# 07-GPS.net
KiCad netlist of a schematic drawn in Altium Designer
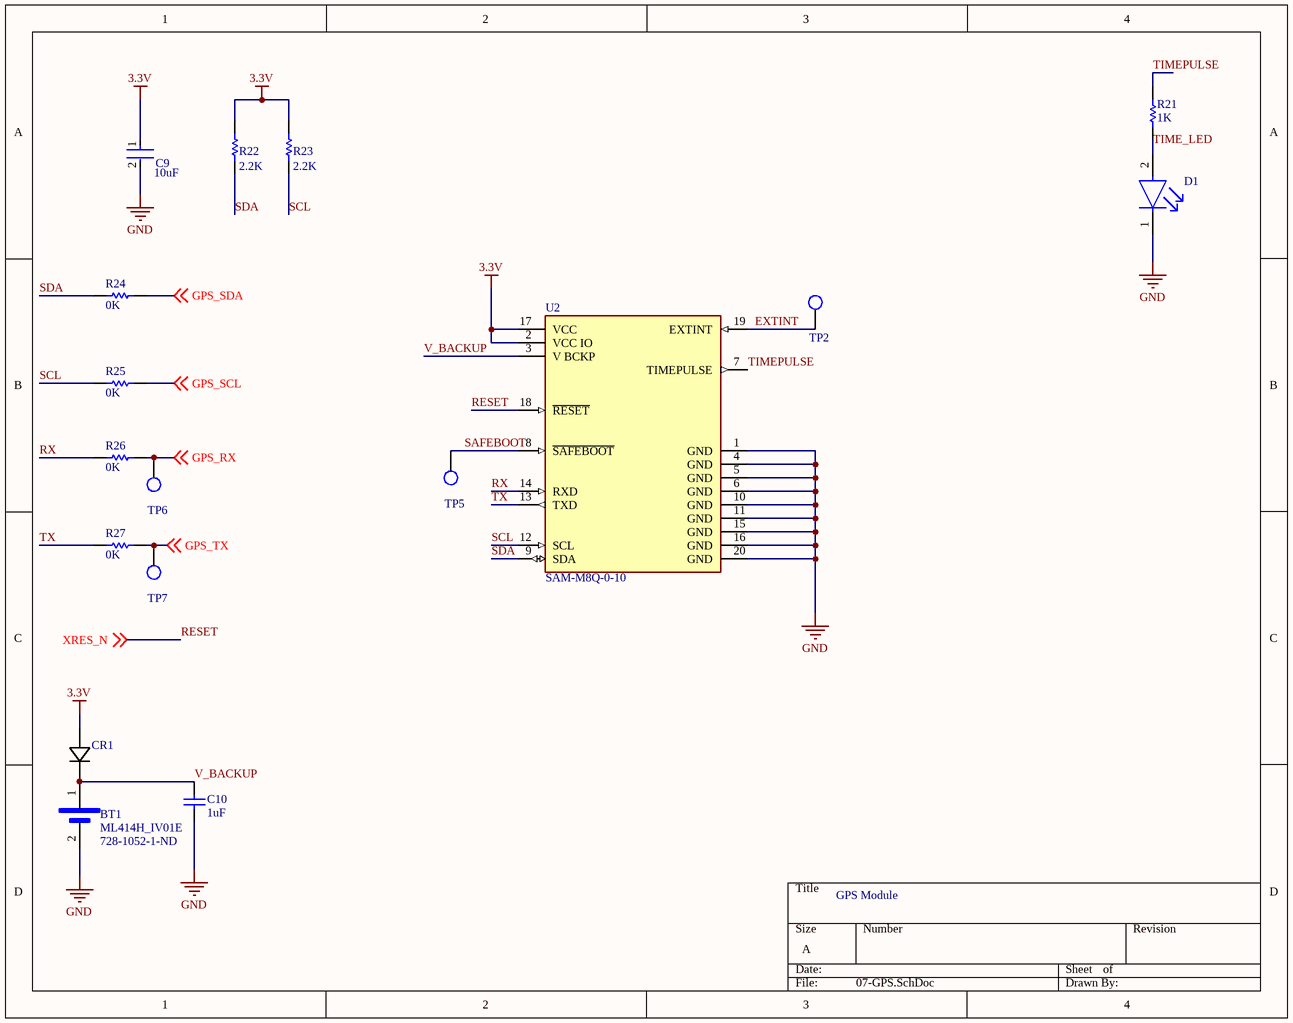
[diagram p0: 07-GPS.SchDoc]

(export (version "E")
  (design (tool "Eeschema 10.0.6"))
  (components
    (comp (ref "BT1")
      (value "ML414H_IV01E")
      (footprint "team6:SEIKO_ML414H_IV01E")
      (description "Coin, 4.8mm 3V Lithium Battery Rechargeable _Secondary_ 1mAh")
      (fields
        (field (name "MP") "ML414H IV01E")
        (field (name "MF") "Seiko Instruments")
        (field (name "SUPPLIER PART NUMBER 1") "728-1052-1-ND")
      )
      (libsource (lib "team6") (part "ML414H_IV01E"))
    )
    (comp (ref "C9")
      (value "CL21A106KQCLNNC")
      (footprint "FP-CL21-IPC_B")
      (description "CL21 Series 0805 10uF 6.3V ±10% Tolerance X5R Multilayer Ceramic Chip Capacitor")
      (fields (field (name "CAPACITANCE") "10uF") (field (name "TOLERANCE") "10%"))
      (libsource (lib "Altium Content Vault") (part "b4654b650e69147ec39a6b967a45e02"))
    )
    (comp (ref "C10")
      (value "1uF")
      (footprint "CAPC2013X145X50LL20T25")
      (fields (field (name "MANUFACTURER") "Kemet") (field (name "PART NUMBER") "C0805C105K4PACTU"))
      (libsource (lib "Altium Content Vault") (part "CAP"))
    )
    (comp (ref "CR1")
      (value "CUS05S40")
      (footprint "USC_TOS")
      (description "No Description Available")
      (fields (field (name "COPYRIGHT") "Copyright (C) 2022 Ultra Librarian. All rights reserved."))
      (libsource (lib "team6") (part "CUS05S40"))
    )
    (comp (ref "D1")
      (value "APHCM2012SYCK-F01")
      (footprint "FP-APHCM2012SYCK-F01-MFG")
      (description "LED YELLOW CLEAR CHIP SMD")
      (libsource (lib "Altium Content Vault") (part "8706943c75ba83719d021d2fdc84c58"))
    )
    (comp (ref "R21")
      (value "1K")
      (footprint "RESC2013X60X35ML10T20")
      (description "Chip Resistor, 1 KOhm, +/- 1%, 125 mW, -55 to 155 degC, 0805 (2012 Metric), RoHS, Tape and Reel")
      (fields (field (name "TOLERANCE") "1%") (field (name "MANUFACTURER") "Yageo"))
      (libsource (lib "Altium Content Vault") (part "RES-2"))
    )
    (comp (ref "R22")
      (value "2.2K")
      (footprint "RESC2013X70X40LL20T20")
      (description "ERJ-6GEYJ222V")
      (fields (field (name "MANUFACTURER") "Panasonic"))
      (libsource (lib "Altium Content Vault") (part "RES"))
    )
    (comp (ref "R23")
      (value "2.2K")
      (footprint "RESC2013X70X40LL20T20")
      (description "ERJ-6GEYJ222V")
      (fields (field (name "MANUFACTURER") "Panasonic"))
      (libsource (lib "Altium Content Vault") (part "RES"))
    )
    (comp (ref "R24")
      (value "0K")
      (footprint "RESC2013X50X30LL20T20")
      (fields (field (name "MANUFACTURER") "Vishay Dale") (field (name "PART NUMBER") "CRCW08050000Z0EA"))
      (libsource (lib "Altium Content Vault") (part "RES"))
    )
    (comp (ref "R25")
      (value "0K")
      (footprint "RESC2013X50X30LL20T20")
      (fields (field (name "MANUFACTURER") "Vishay Dale") (field (name "PART NUMBER") "CRCW08050000Z0EA"))
      (libsource (lib "Altium Content Vault") (part "RES"))
    )
    (comp (ref "R26")
      (value "0K")
      (footprint "RESC2013X50X30LL20T20")
      (fields (field (name "MANUFACTURER") "Vishay Dale") (field (name "PART NUMBER") "CRCW08050000Z0EA"))
      (libsource (lib "Altium Content Vault") (part "RES"))
    )
    (comp (ref "R27")
      (value "0K")
      (footprint "RESC2013X50X30LL20T20")
      (fields (field (name "MANUFACTURER") "Vishay Dale") (field (name "PART NUMBER") "CRCW08050000Z0EA"))
      (libsource (lib "Altium Content Vault") (part "RES"))
    )
    (comp (ref "TP2")
      (value "TP_1206")
      (footprint "TP-SMC-1206")
      (description "Test Point SMD 1206")
      (fields
        (field (name "MANUFACTURER") "TE Connectivity (Tyco Electronics)")
        (field (name "MANUFACTURER PART NUMBER") "1625854-1")
      )
      (libsource (lib "Mechanical") (part "TP_1206"))
    )
    (comp (ref "TP5")
      (value "TP_1206")
      (footprint "TP-SMC-1206")
      (description "Test Point SMD 1206")
      (fields
        (field (name "MANUFACTURER") "TE Connectivity (Tyco Electronics)")
        (field (name "MANUFACTURER PART NUMBER") "1625854-1")
      )
      (libsource (lib "Mechanical") (part "TP_1206"))
    )
    (comp (ref "TP6")
      (value "TP_1206")
      (footprint "TP-SMC-1206")
      (description "Test Point SMD 1206")
      (fields
        (field (name "MANUFACTURER") "TE Connectivity (Tyco Electronics)")
        (field (name "MANUFACTURER PART NUMBER") "1625854-1")
      )
      (libsource (lib "Mechanical") (part "TP_1206"))
    )
    (comp (ref "TP7")
      (value "TP_1206")
      (footprint "TP-SMC-1206")
      (description "Test Point SMD 1206")
      (fields
        (field (name "MANUFACTURER") "TE Connectivity (Tyco Electronics)")
        (field (name "MANUFACTURER PART NUMBER") "1625854-1")
      )
      (libsource (lib "Mechanical") (part "TP_1206"))
    )
    (comp (ref "U2")
      (value "SAM-M8Q-0-10")
      (footprint "FP-SAM-M8Q-0-10-MFG")
      (description "RF RX GALILEO 1.575GHZ/1.602GHZ")
      (fields
        (field (name "MANUFACTURER") "uBlox")
        (field (name "OCTOPART") "https://octopart.com/sam-m8q-0-10-u-blox-88247750")
      )
      (libsource (lib "Altium Content Vault") (part "e897669bc61729ed63f6e62e0b1e840"))
    )
  )
  (nets
    (net (code "1") (name "/EXTINT") (class "Default")
      (node (ref "TP2") (pin "1") (pintype "passive"))
      (node (ref "U2") (pin "19") (pinfunction "EXTINT_19") (pintype "input"))
    )
    (net (code "2") (name "/RX") (class "Default")
      (node (ref "R26") (pin "1") (pinfunction "1_1") (pintype "passive"))
      (node (ref "U2") (pin "14") (pinfunction "RXD_14") (pintype "input"))
    )
    (net (code "3") (name "/SAFEBOOT") (class "Default")
      (node (ref "TP5") (pin "1") (pintype "passive"))
      (node (ref "U2") (pin "8") (pinfunction "~{SAFEBOOT}_8") (pintype "input"))
    )
    (net (code "4") (name "/SCL") (class "Default")
      (node (ref "R23") (pin "1") (pinfunction "1_1") (pintype "passive"))
      (node (ref "R25") (pin "1") (pinfunction "1_1") (pintype "passive"))
      (node (ref "U2") (pin "12") (pinfunction "SCL_12") (pintype "input"))
    )
    (net (code "5") (name "/SDA") (class "Default")
      (node (ref "R22") (pin "1") (pinfunction "1_1") (pintype "passive"))
      (node (ref "R24") (pin "1") (pinfunction "1_1") (pintype "passive"))
      (node (ref "U2") (pin "9") (pinfunction "SDA_9") (pintype "bidirectional"))
    )
    (net (code "6") (name "/TIMEPULSE") (class "Default")
      (node (ref "R21") (pin "2") (pinfunction "2_2") (pintype "passive"))
      (node (ref "U2") (pin "7") (pinfunction "TIMEPULSE_7") (pintype "output"))
    )
    (net (code "7") (name "/TIME_LED") (class "Default")
      (node (ref "D1") (pin "2") (pinfunction "A_2") (pintype "passive"))
      (node (ref "R21") (pin "1") (pinfunction "1_1") (pintype "passive"))
    )
    (net (code "8") (name "/TX") (class "Default")
      (node (ref "R27") (pin "1") (pinfunction "1_1") (pintype "passive"))
      (node (ref "U2") (pin "13") (pinfunction "TXD_13") (pintype "output"))
    )
    (net (code "9") (name "/V_BACKUP") (class "Default")
      (node (ref "BT1") (pin "1") (pinfunction "POS_1") (pintype "passive"))
      (node (ref "C10") (pin "1") (pinfunction "1_1") (pintype "passive"))
      (node (ref "CR1") (pin "1") (pinfunction "cathode_1") (pintype "passive"))
      (node (ref "U2") (pin "3") (pinfunction "V_BCKP_3") (pintype "power_in"))
    )
    (net (code "10") (name "3.3V") (class "Default")
      (node (ref "C9") (pin "1") (pinfunction "1_1") (pintype "passive"))
      (node (ref "CR1") (pin "2") (pinfunction "anode_2") (pintype "passive"))
      (node (ref "R22") (pin "2") (pinfunction "2_2") (pintype "passive"))
      (node (ref "R23") (pin "2") (pinfunction "2_2") (pintype "passive"))
      (node (ref "U2") (pin "17") (pinfunction "VCC_17") (pintype "power_in"))
      (node (ref "U2") (pin "2") (pinfunction "VCC_IO_2") (pintype "power_in"))
    )
    (net (code "11") (name "GND") (class "Default")
      (node (ref "BT1") (pin "2") (pinfunction "NEG_2") (pintype "passive"))
      (node (ref "C10") (pin "2") (pinfunction "2_2") (pintype "passive"))
      (node (ref "C9") (pin "2") (pinfunction "2_2") (pintype "passive"))
      (node (ref "D1") (pin "1") (pinfunction "C_1") (pintype "passive"))
      (node (ref "U2") (pin "1") (pinfunction "GND_1") (pintype "power_in"))
      (node (ref "U2") (pin "10") (pinfunction "GND_10") (pintype "power_in"))
      (node (ref "U2") (pin "11") (pinfunction "GND_11") (pintype "power_in"))
      (node (ref "U2") (pin "15") (pinfunction "GND_15") (pintype "power_in"))
      (node (ref "U2") (pin "16") (pinfunction "GND_16") (pintype "power_in"))
      (node (ref "U2") (pin "20") (pinfunction "GND_20") (pintype "power_in"))
      (node (ref "U2") (pin "4") (pinfunction "GND_4") (pintype "power_in"))
      (node (ref "U2") (pin "5") (pinfunction "GND_5") (pintype "power_in"))
      (node (ref "U2") (pin "6") (pinfunction "GND_6") (pintype "power_in"))
    )
    (net (code "12") (name "GPS_RX") (class "Default")
      (node (ref "R26") (pin "2") (pinfunction "2_2") (pintype "passive"))
      (node (ref "TP6") (pin "1") (pintype "passive"))
    )
    (net (code "13") (name "GPS_SCL") (class "Default")
      (node (ref "R25") (pin "2") (pinfunction "2_2") (pintype "passive"))
    )
    (net (code "14") (name "GPS_SDA") (class "Default")
      (node (ref "R24") (pin "2") (pinfunction "2_2") (pintype "passive"))
    )
    (net (code "15") (name "GPS_TX") (class "Default")
      (node (ref "R27") (pin "2") (pinfunction "2_2") (pintype "passive"))
      (node (ref "TP7") (pin "1") (pintype "passive"))
    )
    (net (code "16") (name "XRES_N") (class "Default")
      (node (ref "U2") (pin "18") (pinfunction "~{RESET}_18") (pintype "input"))
    )
  )
)
